# Peripherals.net
KiCad netlist of a schematic drawn in Altium Designer
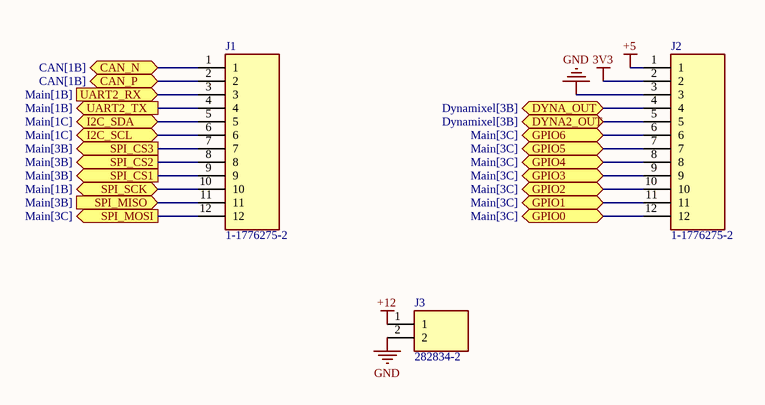
[diagram p0: Peripherals.SchDoc]

(export (version "E")
  (design (tool "Eeschema 10.0.6"))
  (components
    (comp (ref "J1")
      (value "1-1776275-2")
      (footprint "SamacSys:117762752")
      (description "Connector")
      (fields (field (name "MOUSER PART NUMBER") "571-1-1776275-2"))
      (libsource (lib "*") (part "1-1776275-2"))
    )
    (comp (ref "J2")
      (value "1-1776275-2")
      (footprint "SamacSys:117762752")
      (description "Connector")
      (fields (field (name "MOUSER PART NUMBER") "571-1-1776275-2"))
      (libsource (lib "*") (part "1-1776275-2"))
    )
    (comp (ref "J3")
      (value "282834-2")
      (footprint "SamacSys:282834-2_1")
      (description "Connector")
      (fields (field (name "MOUSER PART NUMBER") "571-282834-2"))
      (libsource (lib "*") (part "282834-2"))
    )
  )
  (nets
    (net (code "1") (name "+5") (class "Default")
      (node (ref "J2") (pin "1") (pinfunction "1_1") (pintype "passive"))
    )
    (net (code "2") (name "+12") (class "Default")
      (node (ref "J3") (pin "1") (pinfunction "1_1") (pintype "passive"))
    )
    (net (code "3") (name "/CAN_N") (class "Default")
      (node (ref "J1") (pin "1") (pinfunction "1_1") (pintype "passive"))
    )
    (net (code "4") (name "/CAN_P") (class "Default")
      (node (ref "J1") (pin "2") (pinfunction "2_2") (pintype "passive"))
    )
    (net (code "5") (name "/DYNA2_OUT") (class "Default")
      (node (ref "J2") (pin "5") (pinfunction "5_5") (pintype "passive"))
    )
    (net (code "6") (name "/DYNA_OUT") (class "Default")
      (node (ref "J2") (pin "4") (pinfunction "4_4") (pintype "passive"))
    )
    (net (code "7") (name "/GPIO0") (class "Default")
      (node (ref "J2") (pin "12") (pinfunction "12_12") (pintype "passive"))
    )
    (net (code "8") (name "/GPIO1") (class "Default")
      (node (ref "J2") (pin "11") (pinfunction "11_11") (pintype "passive"))
    )
    (net (code "9") (name "/GPIO2") (class "Default")
      (node (ref "J2") (pin "10") (pinfunction "10_10") (pintype "passive"))
    )
    (net (code "10") (name "/GPIO3") (class "Default")
      (node (ref "J2") (pin "9") (pinfunction "9_9") (pintype "passive"))
    )
    (net (code "11") (name "/GPIO4") (class "Default")
      (node (ref "J2") (pin "8") (pinfunction "8_8") (pintype "passive"))
    )
    (net (code "12") (name "/GPIO5") (class "Default")
      (node (ref "J2") (pin "7") (pinfunction "7_7") (pintype "passive"))
    )
    (net (code "13") (name "/GPIO6") (class "Default")
      (node (ref "J2") (pin "6") (pinfunction "6_6") (pintype "passive"))
    )
    (net (code "14") (name "/I2C_SCL") (class "Default")
      (node (ref "J1") (pin "6") (pinfunction "6_6") (pintype "passive"))
    )
    (net (code "15") (name "/I2C_SDA") (class "Default")
      (node (ref "J1") (pin "5") (pinfunction "5_5") (pintype "passive"))
    )
    (net (code "16") (name "/SPI_CS1") (class "Default")
      (node (ref "J1") (pin "9") (pinfunction "9_9") (pintype "passive"))
    )
    (net (code "17") (name "/SPI_CS2") (class "Default")
      (node (ref "J1") (pin "8") (pinfunction "8_8") (pintype "passive"))
    )
    (net (code "18") (name "/SPI_CS3") (class "Default")
      (node (ref "J1") (pin "7") (pinfunction "7_7") (pintype "passive"))
    )
    (net (code "19") (name "/SPI_MISO") (class "Default")
      (node (ref "J1") (pin "11") (pinfunction "11_11") (pintype "passive"))
    )
    (net (code "20") (name "/SPI_MOSI") (class "Default")
      (node (ref "J1") (pin "12") (pinfunction "12_12") (pintype "passive"))
    )
    (net (code "21") (name "/SPI_SCK") (class "Default")
      (node (ref "J1") (pin "10") (pinfunction "10_10") (pintype "passive"))
    )
    (net (code "22") (name "/UART2_RX") (class "Default")
      (node (ref "J1") (pin "3") (pinfunction "3_3") (pintype "passive"))
    )
    (net (code "23") (name "/UART2_TX") (class "Default")
      (node (ref "J1") (pin "4") (pinfunction "4_4") (pintype "passive"))
    )
    (net (code "24") (name "3V3") (class "Default")
      (node (ref "J2") (pin "2") (pinfunction "2_2") (pintype "passive"))
    )
    (net (code "25") (name "GND") (class "Default")
      (node (ref "J2") (pin "3") (pinfunction "3_3") (pintype "passive"))
      (node (ref "J3") (pin "2") (pinfunction "2_2") (pintype "passive"))
    )
  )
)
